# ProProject_stepper_music_2024-12-04.net
KiCad netlist of a schematic drawn in EasyEDA Pro
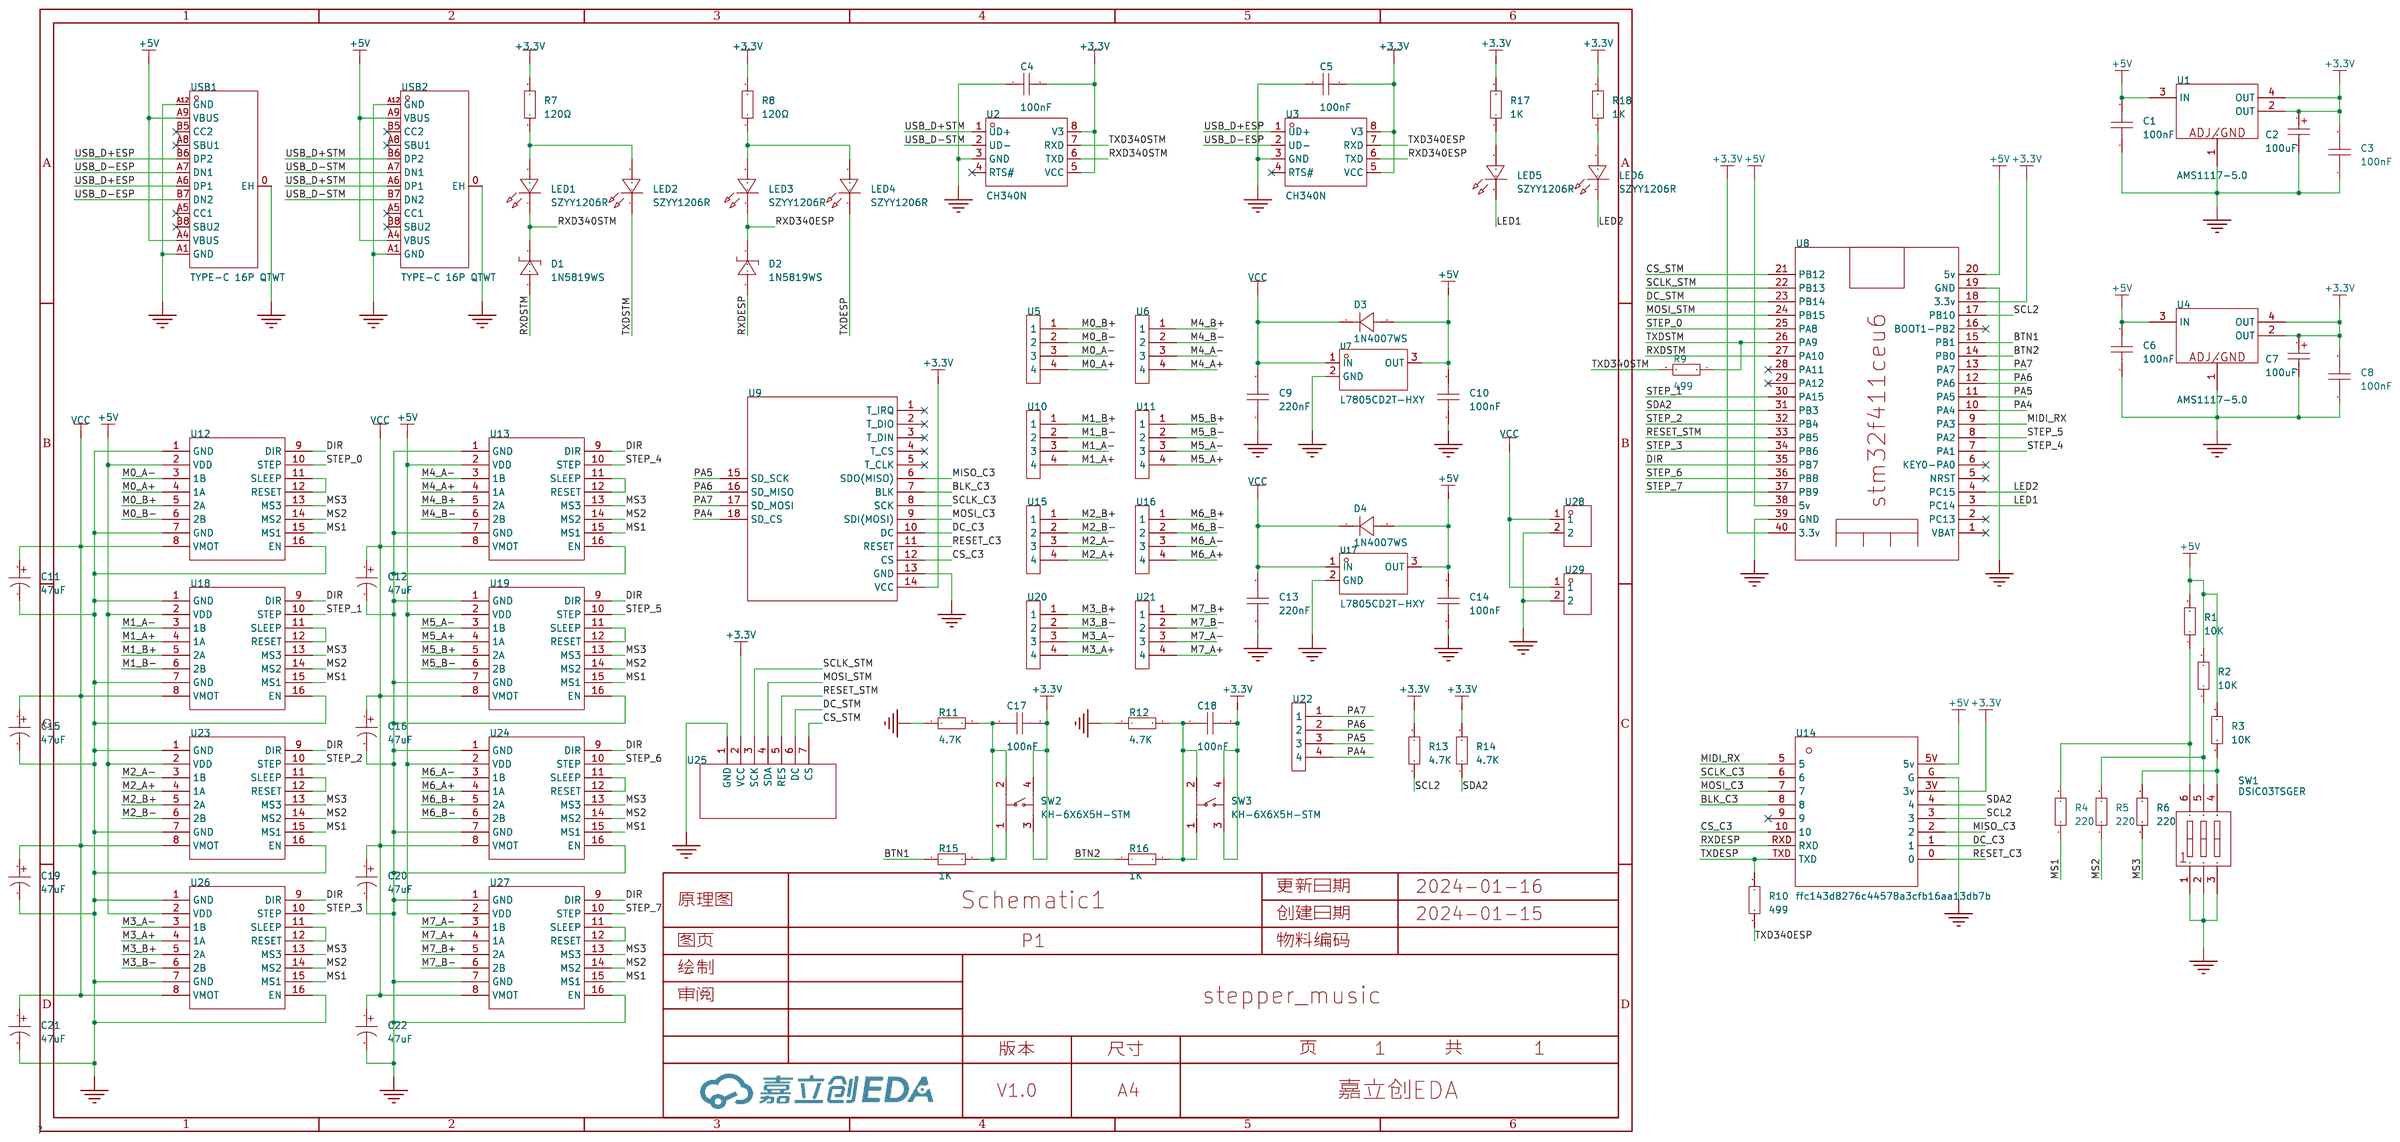
[diagram p0: schematic sheet]

(export (version "E")
  (design (tool "Eeschema 10.0.6"))
  (components
    (comp (ref "C1")
      (value "100nF")
      (footprint "easyedapro:C0603")
      (libsource (lib "easyedapro") (part "CapAcitance"))
    )
    (comp (ref "C2")
      (value "100uF")
      (footprint "easyedapro:CASE-D_7343")
      (description "容值:330uF;精度:±10%;额定电压:10V;等效串联电阻:900mΩ@100kHz;工作温度:-55°C~+125°C;")
      (fields (field (name "Manufacturer Part") "TAJD337K010RNJ") (field (name "Manufacturer") "Kyocera AVX"))
      (libsource (lib "easyedapro") (part "TAJD337K010RNJ"))
    )
    (comp (ref "C3")
      (value "100nF")
      (footprint "easyedapro:C0603")
      (libsource (lib "easyedapro") (part "CapAcitance"))
    )
    (comp (ref "C4")
      (value "100nF")
      (footprint "easyedapro:C0402")
      (description "容值:100nF;精度:±10%;额定电压:16V;材质(温度系数):X7R;")
      (fields
        (field (name "Manufacturer Part") "CL05B104KO5NNNC")
        (field (name "Manufacturer") "SAMSUNG(三星)")
      )
      (libsource (lib "easyedapro") (part "CL05B104KO5NNNC"))
    )
    (comp (ref "C5")
      (value "100nF")
      (footprint "easyedapro:C0402")
      (description "容值:100nF;精度:±10%;额定电压:16V;材质(温度系数):X7R;")
      (fields
        (field (name "Manufacturer Part") "CL05B104KO5NNNC")
        (field (name "Manufacturer") "SAMSUNG(三星)")
      )
      (libsource (lib "easyedapro") (part "CL05B104KO5NNNC"))
    )
    (comp (ref "C6")
      (value "100nF")
      (footprint "easyedapro:C0603")
      (libsource (lib "easyedapro") (part "CapAcitance"))
    )
    (comp (ref "C7")
      (value "100uF")
      (footprint "easyedapro:CASE-D_7343")
      (description "容值:330uF;精度:±10%;额定电压:10V;等效串联电阻:900mΩ@100kHz;工作温度:-55°C~+125°C;")
      (fields (field (name "Manufacturer Part") "TAJD337K010RNJ") (field (name "Manufacturer") "Kyocera AVX"))
      (libsource (lib "easyedapro") (part "TAJD337K010RNJ"))
    )
    (comp (ref "C8")
      (value "100nF")
      (footprint "easyedapro:C0603")
      (libsource (lib "easyedapro") (part "CapAcitance"))
    )
    (comp (ref "C9")
      (value "220nF")
      (footprint "easyedapro:C0603")
      (libsource (lib "easyedapro") (part "CapAcitance"))
    )
    (comp (ref "C10")
      (value "100nF")
      (footprint "easyedapro:C0603")
      (libsource (lib "easyedapro") (part "CapAcitance"))
    )
    (comp (ref "C11")
      (value "47uF")
      (footprint "easyedapro:CAP-TH_BD6.3-P2.50-D1.0-FD")
      (description "容值:47uF;精度:±20%;额定电压:50V;")
      (fields
        (field (name "Manufacturer Part") "KM476M050E11RR0VH2FP0")
        (field (name "Manufacturer") "CX(承兴)")
      )
      (libsource (lib "easyedapro") (part "47uF 50V 6.3*11_C45101"))
    )
    (comp (ref "C12")
      (value "47uF")
      (footprint "easyedapro:CAP-TH_BD6.3-P2.50-D1.0-FD")
      (description "容值:47uF;精度:±20%;额定电压:50V;")
      (fields
        (field (name "Manufacturer Part") "KM476M050E11RR0VH2FP0")
        (field (name "Manufacturer") "CX(承兴)")
      )
      (libsource (lib "easyedapro") (part "47uF 50V 6.3*11_C45101"))
    )
    (comp (ref "C13")
      (value "220nF")
      (footprint "easyedapro:C0603")
      (libsource (lib "easyedapro") (part "CapAcitance"))
    )
    (comp (ref "C14")
      (value "100nF")
      (footprint "easyedapro:C0603")
      (libsource (lib "easyedapro") (part "CapAcitance"))
    )
    (comp (ref "C15")
      (value "47uF")
      (footprint "easyedapro:CAP-TH_BD6.3-P2.50-D1.0-FD")
      (description "容值:47uF;精度:±20%;额定电压:50V;")
      (fields
        (field (name "Manufacturer Part") "KM476M050E11RR0VH2FP0")
        (field (name "Manufacturer") "CX(承兴)")
      )
      (libsource (lib "easyedapro") (part "47uF 50V 6.3*11_C45101"))
    )
    (comp (ref "C16")
      (value "47uF")
      (footprint "easyedapro:CAP-TH_BD6.3-P2.50-D1.0-FD")
      (description "容值:47uF;精度:±20%;额定电压:50V;")
      (fields
        (field (name "Manufacturer Part") "KM476M050E11RR0VH2FP0")
        (field (name "Manufacturer") "CX(承兴)")
      )
      (libsource (lib "easyedapro") (part "47uF 50V 6.3*11_C45101"))
    )
    (comp (ref "C17")
      (value "100nF")
      (footprint "easyedapro:C0603")
      (libsource (lib "easyedapro") (part "CapAcitance"))
    )
    (comp (ref "C18")
      (value "100nF")
      (footprint "easyedapro:C0603")
      (libsource (lib "easyedapro") (part "CapAcitance"))
    )
    (comp (ref "C19")
      (value "47uF")
      (footprint "easyedapro:CAP-TH_BD6.3-P2.50-D1.0-FD")
      (description "容值:47uF;精度:±20%;额定电压:50V;")
      (fields
        (field (name "Manufacturer Part") "KM476M050E11RR0VH2FP0")
        (field (name "Manufacturer") "CX(承兴)")
      )
      (libsource (lib "easyedapro") (part "47uF 50V 6.3*11_C45101"))
    )
    (comp (ref "C20")
      (value "47uF")
      (footprint "easyedapro:CAP-TH_BD6.3-P2.50-D1.0-FD")
      (description "容值:47uF;精度:±20%;额定电压:50V;")
      (fields
        (field (name "Manufacturer Part") "KM476M050E11RR0VH2FP0")
        (field (name "Manufacturer") "CX(承兴)")
      )
      (libsource (lib "easyedapro") (part "47uF 50V 6.3*11_C45101"))
    )
    (comp (ref "C21")
      (value "47uF")
      (footprint "easyedapro:CAP-TH_BD6.3-P2.50-D1.0-FD")
      (description "容值:47uF;精度:±20%;额定电压:50V;")
      (fields
        (field (name "Manufacturer Part") "KM476M050E11RR0VH2FP0")
        (field (name "Manufacturer") "CX(承兴)")
      )
      (libsource (lib "easyedapro") (part "47uF 50V 6.3*11_C45101"))
    )
    (comp (ref "C22")
      (value "47uF")
      (footprint "easyedapro:CAP-TH_BD6.3-P2.50-D1.0-FD")
      (description "容值:47uF;精度:±20%;额定电压:50V;")
      (fields
        (field (name "Manufacturer Part") "KM476M050E11RR0VH2FP0")
        (field (name "Manufacturer") "CX(承兴)")
      )
      (libsource (lib "easyedapro") (part "47uF 50V 6.3*11_C45101"))
    )
    (comp (ref "D1")
      (value "1N5819WS")
      (footprint "easyedapro:SOD-323_L1.8-W1.3-LS2.5-RD")
      (description "直流反向耐压(Vr):40V;平均整流电流(Io):1A;正向压降(Vf):600mV@1A;")
      (fields (field (name "Manufacturer") "Hottech(合科泰)"))
      (libsource (lib "easyedapro") (part "1N5819WS"))
    )
    (comp (ref "D2")
      (value "1N5819WS")
      (footprint "easyedapro:SOD-323_L1.8-W1.3-LS2.5-RD")
      (description "直流反向耐压(Vr):40V;平均整流电流(Io):1A;正向压降(Vf):600mV@1A;")
      (fields (field (name "Manufacturer") "Hottech(合科泰)"))
      (libsource (lib "easyedapro") (part "1N5819WS"))
    )
    (comp (ref "D3")
      (value "1N4007WS")
      (footprint "easyedapro:SOD-323_L1.6-W1.3-LS2.7-RD")
      (description "二极管配置:-;正向压降(Vf):1V@50mA;直流反向耐压(Vr):300V;平均整流电流(Io):300mA;")
      (fields (field (name "Manufacturer") "JSMSEMI(杰盛微)"))
      (libsource (lib "easyedapro") (part "1N4007WS_C2687395"))
    )
    (comp (ref "D4")
      (value "1N4007WS")
      (footprint "easyedapro:SOD-323_L1.6-W1.3-LS2.7-RD")
      (description "二极管配置:-;正向压降(Vf):1V@50mA;直流反向耐压(Vr):300V;平均整流电流(Io):300mA;")
      (fields (field (name "Manufacturer") "JSMSEMI(杰盛微)"))
      (libsource (lib "easyedapro") (part "1N4007WS_C2687395"))
    )
    (comp (ref "LED1")
      (value "SZYY1206R")
      (footprint "easyedapro:LED1206-RD-R_RED")
      (description "发光颜色:红灯;二极管配置:-;主波长:615nm~630nm;色温:-;功率:40mW;安装方式:-;")
      (fields (field (name "Manufacturer") "yongyu(永裕光电)"))
      (libsource (lib "easyedapro") (part "SZYY1206R"))
    )
    (comp (ref "LED2")
      (value "SZYY1206R")
      (footprint "easyedapro:LED1206-RD-R_RED")
      (description "发光颜色:红灯;二极管配置:-;主波长:615nm~630nm;色温:-;功率:40mW;安装方式:-;")
      (fields (field (name "Manufacturer") "yongyu(永裕光电)"))
      (libsource (lib "easyedapro") (part "SZYY1206R"))
    )
    (comp (ref "LED3")
      (value "SZYY1206R")
      (footprint "easyedapro:LED1206-RD-R_RED")
      (description "发光颜色:红灯;二极管配置:-;主波长:615nm~630nm;色温:-;功率:40mW;安装方式:-;")
      (fields (field (name "Manufacturer") "yongyu(永裕光电)"))
      (libsource (lib "easyedapro") (part "SZYY1206R"))
    )
    (comp (ref "LED4")
      (value "SZYY1206R")
      (footprint "easyedapro:LED1206-RD-R_RED")
      (description "发光颜色:红灯;二极管配置:-;主波长:615nm~630nm;色温:-;功率:40mW;安装方式:-;")
      (fields (field (name "Manufacturer") "yongyu(永裕光电)"))
      (libsource (lib "easyedapro") (part "SZYY1206R"))
    )
    (comp (ref "LED5")
      (value "SZYY1206R")
      (footprint "easyedapro:LED1206-RD-R_RED")
      (description "发光颜色:红灯;二极管配置:-;主波长:615nm~630nm;色温:-;功率:40mW;安装方式:-;")
      (fields (field (name "Manufacturer") "yongyu(永裕光电)"))
      (libsource (lib "easyedapro") (part "SZYY1206R"))
    )
    (comp (ref "LED6")
      (value "SZYY1206R")
      (footprint "easyedapro:LED1206-RD-R_RED")
      (description "发光颜色:红灯;二极管配置:-;主波长:615nm~630nm;色温:-;功率:40mW;安装方式:-;")
      (fields (field (name "Manufacturer") "yongyu(永裕光电)"))
      (libsource (lib "easyedapro") (part "SZYY1206R"))
    )
    (comp (ref "R1") (value "10K") (footprint "easyedapro:R0603") (libsource (lib "easyedapro") (part "电阻")))
    (comp (ref "R2") (value "10K") (footprint "easyedapro:R0603") (libsource (lib "easyedapro") (part "电阻")))
    (comp (ref "R3") (value "10K") (footprint "easyedapro:R0603") (libsource (lib "easyedapro") (part "电阻")))
    (comp (ref "R4") (value "220") (footprint "easyedapro:R0603") (libsource (lib "easyedapro") (part "电阻")))
    (comp (ref "R5") (value "220") (footprint "easyedapro:R0603") (libsource (lib "easyedapro") (part "电阻")))
    (comp (ref "R6") (value "220") (footprint "easyedapro:R0603") (libsource (lib "easyedapro") (part "电阻")))
    (comp (ref "R7")
      (value "120Ω")
      (footprint "easyedapro:R0603")
      (description "电阻类型:厚膜电阻;阻值:120Ω;精度:±1%;功率:100mW;")
      (fields
        (field (name "Manufacturer Part") "0603WAF1200T5E")
        (field (name "Manufacturer") "UNI-ROYAL(厚声)")
      )
      (libsource (lib "easyedapro") (part "0603WAF1200T5E"))
    )
    (comp (ref "R8")
      (value "120Ω")
      (footprint "easyedapro:R0603")
      (description "电阻类型:厚膜电阻;阻值:120Ω;精度:±1%;功率:100mW;")
      (fields
        (field (name "Manufacturer Part") "0603WAF1200T5E")
        (field (name "Manufacturer") "UNI-ROYAL(厚声)")
      )
      (libsource (lib "easyedapro") (part "0603WAF1200T5E"))
    )
    (comp (ref "R9") (value "499") (footprint "easyedapro:R0603") (libsource (lib "easyedapro") (part "电阻")))
    (comp (ref "R10") (value "499") (footprint "easyedapro:R0603") (libsource (lib "easyedapro") (part "电阻")))
    (comp (ref "R11")
      (value "4.7K")
      (footprint "easyedapro:R0603")
      (libsource (lib "easyedapro") (part "电阻"))
    )
    (comp (ref "R12")
      (value "4.7K")
      (footprint "easyedapro:R0603")
      (libsource (lib "easyedapro") (part "电阻"))
    )
    (comp (ref "R13")
      (value "4.7K")
      (footprint "easyedapro:R0603")
      (libsource (lib "easyedapro") (part "电阻"))
    )
    (comp (ref "R14")
      (value "4.7K")
      (footprint "easyedapro:R0603")
      (libsource (lib "easyedapro") (part "电阻"))
    )
    (comp (ref "R15") (value "1K") (footprint "easyedapro:R0603") (libsource (lib "easyedapro") (part "电阻")))
    (comp (ref "R16") (value "1K") (footprint "easyedapro:R0603") (libsource (lib "easyedapro") (part "电阻")))
    (comp (ref "R17") (value "1K") (footprint "easyedapro:R0603") (libsource (lib "easyedapro") (part "电阻")))
    (comp (ref "R18") (value "1K") (footprint "easyedapro:R0603") (libsource (lib "easyedapro") (part "电阻")))
    (comp (ref "SW1")
      (value "DSIC03TSGER")
      (footprint "easyedapro:SW-SMD_3P-L7.6-W6.0-P2.54-LS9.3-BL")
      (description "电路结构:单刀单掷;开关位数:3位;额定电流:25mA;额定电压:24V;使用寿命:3千次;颜色:黑色;")
      (fields (field (name "Manufacturer") "康深"))
      (libsource (lib "easyedapro") (part "DSIC03TSGER"))
    )
    (comp (ref "SW2")
      (value "KH-6X6X5H-STM")
      (footprint "easyedapro:SW-SMD_4P-L6.0-W6.0-P4.50-LS9.0-2")
      (description "电路结构:单刀单掷;带支架:否;触点电流:50mA;额定电压(DC):12V;安装方式:立贴;机械寿命:8万次;")
      (fields (field (name "Manufacturer") "kinghelm(金航标)"))
      (libsource (lib "easyedapro") (part "KH-6X6X5H-STM"))
    )
    (comp (ref "SW3")
      (value "KH-6X6X5H-STM")
      (footprint "easyedapro:SW-SMD_4P-L6.0-W6.0-P4.50-LS9.0-2")
      (description "电路结构:单刀单掷;带支架:否;触点电流:50mA;额定电压(DC):12V;安装方式:立贴;机械寿命:8万次;")
      (fields (field (name "Manufacturer") "kinghelm(金航标)"))
      (libsource (lib "easyedapro") (part "KH-6X6X5H-STM"))
    )
    (comp (ref "U1")
      (value "AMS1117-5.0")
      (footprint "easyedapro:SOT-223-3_L6.4-W3.5-P2.30-LS7.0-BR")
      (fields (field (name "Manufacturer") "国芯佳品"))
      (libsource (lib "easyedapro") (part "AMS1117-5.0_C2992571"))
    )
    (comp (ref "U2")
      (value "CH340N")
      (footprint "easyedapro:SOP-8_L4.9-W3.9-P1.27-LS6.0-BL")
      (fields (field (name "Manufacturer") "WCH(南京沁恒)"))
      (libsource (lib "easyedapro") (part "CH340N_C2977777"))
    )
    (comp (ref "U3")
      (value "CH340N")
      (footprint "easyedapro:SOP-8_L4.9-W3.9-P1.27-LS6.0-BL")
      (fields (field (name "Manufacturer") "WCH(南京沁恒)"))
      (libsource (lib "easyedapro") (part "CH340N_C2977777"))
    )
    (comp (ref "U4")
      (value "AMS1117-5.0")
      (footprint "easyedapro:SOT-223-3_L6.4-W3.5-P2.30-LS7.0-BR")
      (fields (field (name "Manufacturer") "国芯佳品"))
      (libsource (lib "easyedapro") (part "AMS1117-5.0_C2992571"))
    )
    (comp (ref "U5")
      (value "~")
      (footprint "easyedapro:2.54 - 4P")
      (description "间距2.54排针 4P")
      (libsource (lib "easyedapro") (part "2.54 - 4P"))
    )
    (comp (ref "U6")
      (value "~")
      (footprint "easyedapro:2.54 - 4P")
      (description "间距2.54排针 4P")
      (libsource (lib "easyedapro") (part "2.54 - 4P"))
    )
    (comp (ref "U7")
      (value "L7805CD2T-HXY")
      (footprint "easyedapro:TO-263-2_L10.2-W8.5-P2.54-LS15.2-TL")
      (description "输出类型:固定;最大输入电压:35V;输出电压:5V;输出电流:1A;输出极性:正;")
      (fields (field (name "Manufacturer") "HXY MOSFET(华轩阳电子)"))
      (libsource (lib "easyedapro") (part "L7805CD2T-HXY"))
    )
    (comp (ref "U8")
      (value "~")
      (footprint "easyedapro:stm32f411ceu6")
      (description "stm32f411ceu6\nhttps://www.taobao.com/list/item/594670660262.htm")
      (libsource (lib "easyedapro") (part "stm3f411ceu6"))
    )
    (comp (ref "U9")
      (value "~")
      (description "Driver: ILI9341")
      (libsource (lib "easyedapro") (part "2.8inch TFT LCD"))
    )
    (comp (ref "U10")
      (value "~")
      (footprint "easyedapro:2.54 - 4P")
      (description "间距2.54排针 4P")
      (libsource (lib "easyedapro") (part "2.54 - 4P"))
    )
    (comp (ref "U11")
      (value "~")
      (footprint "easyedapro:2.54 - 4P")
      (description "间距2.54排针 4P")
      (libsource (lib "easyedapro") (part "2.54 - 4P"))
    )
    (comp (ref "U12")
      (value "~")
      (footprint "easyedapro:a4988 module")
      (description "a4988 stepper motor driver module")
      (libsource (lib "easyedapro") (part "a4988"))
    )
    (comp (ref "U13")
      (value "~")
      (footprint "easyedapro:a4988 module")
      (description "a4988 stepper motor driver module")
      (libsource (lib "easyedapro") (part "a4988"))
    )
    (comp (ref "U14")
      (value "ffc143d8276c44578a3cfb16aa13db7b")
      (footprint "easyedapro:esp32c3-mini")
      (description "esp32c3-mini No-logo")
      (libsource (lib "easyedapro") (part "esp32c3_super_mini"))
    )
    (comp (ref "U15")
      (value "~")
      (footprint "easyedapro:2.54 - 4P")
      (description "间距2.54排针 4P")
      (libsource (lib "easyedapro") (part "2.54 - 4P"))
    )
    (comp (ref "U16")
      (value "~")
      (footprint "easyedapro:2.54 - 4P")
      (description "间距2.54排针 4P")
      (libsource (lib "easyedapro") (part "2.54 - 4P"))
    )
    (comp (ref "U17")
      (value "L7805CD2T-HXY")
      (footprint "easyedapro:TO-263-2_L10.2-W8.5-P2.54-LS15.2-TL")
      (description "输出类型:固定;最大输入电压:35V;输出电压:5V;输出电流:1A;输出极性:正;")
      (fields (field (name "Manufacturer") "HXY MOSFET(华轩阳电子)"))
      (libsource (lib "easyedapro") (part "L7805CD2T-HXY"))
    )
    (comp (ref "U18")
      (value "~")
      (footprint "easyedapro:a4988 module")
      (description "a4988 stepper motor driver module")
      (libsource (lib "easyedapro") (part "a4988"))
    )
    (comp (ref "U19")
      (value "~")
      (footprint "easyedapro:a4988 module")
      (description "a4988 stepper motor driver module")
      (libsource (lib "easyedapro") (part "a4988"))
    )
    (comp (ref "U20")
      (value "~")
      (footprint "easyedapro:2.54 - 4P")
      (description "间距2.54排针 4P")
      (libsource (lib "easyedapro") (part "2.54 - 4P"))
    )
    (comp (ref "U21")
      (value "~")
      (footprint "easyedapro:2.54 - 4P")
      (description "间距2.54排针 4P")
      (libsource (lib "easyedapro") (part "2.54 - 4P"))
    )
    (comp (ref "U22")
      (value "~")
      (footprint "easyedapro:2.54 - 4P")
      (description "间距2.54排针 4P")
      (libsource (lib "easyedapro") (part "2.54 - 4P"))
    )
    (comp (ref "U23")
      (value "~")
      (footprint "easyedapro:a4988 module")
      (description "a4988 stepper motor driver module")
      (libsource (lib "easyedapro") (part "a4988"))
    )
    (comp (ref "U24")
      (value "~")
      (footprint "easyedapro:a4988 module")
      (description "a4988 stepper motor driver module")
      (libsource (lib "easyedapro") (part "a4988"))
    )
    (comp (ref "U25")
      (value "~")
      (footprint "easyedapro:1.3inch OLED module")
      (description "SH1106 Driver 128*64")
      (libsource (lib "easyedapro") (part "1.3 inch OLED"))
    )
    (comp (ref "U26")
      (value "~")
      (footprint "easyedapro:a4988 module")
      (description "a4988 stepper motor driver module")
      (libsource (lib "easyedapro") (part "a4988"))
    )
    (comp (ref "U27")
      (value "~")
      (footprint "easyedapro:a4988 module")
      (description "a4988 stepper motor driver module")
      (libsource (lib "easyedapro") (part "a4988"))
    )
    (comp (ref "U28")
      (value "={Manufacturer Part} /")
      (footprint "easyedapro:CONN-TH_2P-P5.00_L7.6-W10.0")
      (fields
        (field (name "Manufacturer Part") "DB301V-5.0-2P-BU-S")
        (field (name "Manufacturer") "DIBO(地博电气)")
      )
      (libsource (lib "easyedapro") (part "DB301V-5.0-2P"))
    )
    (comp (ref "U29")
      (value "={Manufacturer Part} /")
      (footprint "easyedapro:CONN-TH_2P-P5.00_L7.6-W10.0")
      (fields
        (field (name "Manufacturer Part") "DB301V-5.0-2P-BU-S")
        (field (name "Manufacturer") "DIBO(地博电气)")
      )
      (libsource (lib "easyedapro") (part "DB301V-5.0-2P"))
    )
    (comp (ref "USB1")
      (value "TYPE-C 16P QTWT")
      (footprint "easyedapro:USB-TYPE-C-SMD_TYPE-C-16P-QTWT")
      (fields (field (name "Manufacturer") "SHOU HAN(首韩)"))
      (libsource (lib "easyedapro") (part "TYPE-C 16P QTWT"))
    )
    (comp (ref "USB2")
      (value "TYPE-C 16P QTWT")
      (footprint "easyedapro:USB-TYPE-C-SMD_TYPE-C-16P-QTWT")
      (fields (field (name "Manufacturer") "SHOU HAN(首韩)"))
      (libsource (lib "easyedapro") (part "TYPE-C 16P QTWT"))
    )
  )
  (nets
    (net (code "1") (name "+3.3V") (class "Default")
      (node (ref "C17") (pin "2") (pinfunction "2_2") (pintype "input"))
      (node (ref "C18") (pin "2") (pinfunction "2_2") (pintype "input"))
      (node (ref "C2") (pin "1") (pinfunction "1_1") (pintype "input"))
      (node (ref "C3") (pin "2") (pinfunction "2_2") (pintype "input"))
      (node (ref "C4") (pin "2") (pinfunction "2_2") (pintype "input"))
      (node (ref "C5") (pin "2") (pinfunction "2_2") (pintype "input"))
      (node (ref "C7") (pin "1") (pinfunction "1_1") (pintype "input"))
      (node (ref "C8") (pin "2") (pinfunction "2_2") (pintype "input"))
      (node (ref "R13") (pin "2") (pinfunction "2_2") (pintype "input"))
      (node (ref "R14") (pin "2") (pinfunction "2_2") (pintype "input"))
      (node (ref "R17") (pin "2") (pinfunction "2_2") (pintype "input"))
      (node (ref "R18") (pin "2") (pinfunction "2_2") (pintype "input"))
      (node (ref "R7") (pin "2") (pinfunction "2_2") (pintype "input"))
      (node (ref "R8") (pin "2") (pinfunction "2_2") (pintype "input"))
      (node (ref "SW2") (pin "3") (pinfunction "3_3") (pintype "unspecified"))
      (node (ref "SW2") (pin "4") (pinfunction "4_4") (pintype "unspecified"))
      (node (ref "SW3") (pin "3") (pinfunction "3_3") (pintype "unspecified"))
      (node (ref "SW3") (pin "4") (pinfunction "4_4") (pintype "unspecified"))
      (node (ref "U1") (pin "2") (pinfunction "OUT_2") (pintype "unspecified"))
      (node (ref "U1") (pin "4") (pinfunction "OUT_4") (pintype "unspecified"))
      (node (ref "U14") (pin "3V") (pinfunction "3v_3V") (pintype "input"))
      (node (ref "U2") (pin "5") (pinfunction "VCC_5") (pintype "input"))
      (node (ref "U2") (pin "8") (pinfunction "V3_8") (pintype "input"))
      (node (ref "U25") (pin "2") (pinfunction "VCC_2") (pintype "input"))
      (node (ref "U3") (pin "5") (pinfunction "VCC_5") (pintype "input"))
      (node (ref "U3") (pin "8") (pinfunction "V3_8") (pintype "input"))
      (node (ref "U4") (pin "2") (pinfunction "OUT_2") (pintype "unspecified"))
      (node (ref "U4") (pin "4") (pinfunction "OUT_4") (pintype "unspecified"))
      (node (ref "U8") (pin "18") (pinfunction "3.3v_18") (pintype "input"))
      (node (ref "U8") (pin "40") (pinfunction "3.3v_40") (pintype "input"))
      (node (ref "U9") (pin "14") (pinfunction "VCC_14") (pintype "input"))
    )
    (net (code "2") (name "+5V") (class "Default")
      (node (ref "C1") (pin "2") (pinfunction "2_2") (pintype "input"))
      (node (ref "C10") (pin "2") (pinfunction "2_2") (pintype "input"))
      (node (ref "C14") (pin "2") (pinfunction "2_2") (pintype "input"))
      (node (ref "C6") (pin "2") (pinfunction "2_2") (pintype "input"))
      (node (ref "D3") (pin "2") (pinfunction "A_2") (pintype "unspecified"))
      (node (ref "D4") (pin "2") (pinfunction "A_2") (pintype "unspecified"))
      (node (ref "R1") (pin "2") (pinfunction "2_2") (pintype "input"))
      (node (ref "R2") (pin "2") (pinfunction "2_2") (pintype "input"))
      (node (ref "R3") (pin "2") (pinfunction "2_2") (pintype "input"))
      (node (ref "U1") (pin "3") (pinfunction "IN_3") (pintype "unspecified"))
      (node (ref "U12") (pin "2") (pinfunction "VDD_2") (pintype "input"))
      (node (ref "U13") (pin "2") (pinfunction "VDD_2") (pintype "input"))
      (node (ref "U14") (pin "5V") (pinfunction "5v_5V") (pintype "input"))
      (node (ref "U17") (pin "3") (pinfunction "OUT_3") (pintype "input"))
      (node (ref "U18") (pin "2") (pinfunction "VDD_2") (pintype "input"))
      (node (ref "U19") (pin "2") (pinfunction "VDD_2") (pintype "input"))
      (node (ref "U23") (pin "2") (pinfunction "VDD_2") (pintype "input"))
      (node (ref "U24") (pin "2") (pinfunction "VDD_2") (pintype "input"))
      (node (ref "U26") (pin "2") (pinfunction "VDD_2") (pintype "input"))
      (node (ref "U27") (pin "2") (pinfunction "VDD_2") (pintype "input"))
      (node (ref "U4") (pin "3") (pinfunction "IN_3") (pintype "unspecified"))
      (node (ref "U7") (pin "3") (pinfunction "OUT_3") (pintype "input"))
      (node (ref "U8") (pin "20") (pinfunction "5v_20") (pintype "input"))
      (node (ref "U8") (pin "38") (pinfunction "5v_38") (pintype "input"))
      (node (ref "USB1") (pin "A4") (pinfunction "VBUS_A4") (pintype "unspecified"))
      (node (ref "USB1") (pin "A9") (pinfunction "VBUS_A9") (pintype "unspecified"))
      (node (ref "USB2") (pin "A4") (pinfunction "VBUS_A4") (pintype "unspecified"))
      (node (ref "USB2") (pin "A9") (pinfunction "VBUS_A9") (pintype "unspecified"))
    )
    (net (code "3") (name "/BLK_C3") (class "Default")
      (node (ref "U14") (pin "8") (pinfunction "8_8") (pintype "input"))
      (node (ref "U9") (pin "7") (pinfunction "BLK_7") (pintype "input"))
    )
    (net (code "4") (name "/BTN1") (class "Default")
      (node (ref "R15") (pin "1") (pinfunction "1_1") (pintype "input"))
      (node (ref "U8") (pin "15") (pinfunction "PB1_15") (pintype "input"))
    )
    (net (code "5") (name "/BTN2") (class "Default")
      (node (ref "R16") (pin "1") (pinfunction "1_1") (pintype "input"))
      (node (ref "U8") (pin "14") (pinfunction "PB0_14") (pintype "input"))
    )
    (net (code "6") (name "/CS_C3") (class "Default")
      (node (ref "U14") (pin "10") (pinfunction "10_10") (pintype "input"))
      (node (ref "U9") (pin "12") (pinfunction "CS_12") (pintype "input"))
    )
    (net (code "7") (name "/CS_STM") (class "Default")
      (node (ref "U25") (pin "7") (pinfunction "CS_7") (pintype "input"))
      (node (ref "U8") (pin "21") (pinfunction "PB12_21") (pintype "input"))
    )
    (net (code "8") (name "/DC_C3") (class "Default")
      (node (ref "U14") (pin "1") (pinfunction "1_1") (pintype "bidirectional"))
      (node (ref "U9") (pin "10") (pinfunction "DC_10") (pintype "input"))
    )
    (net (code "9") (name "/DC_STM") (class "Default")
      (node (ref "U25") (pin "6") (pinfunction "DC_6") (pintype "input"))
      (node (ref "U8") (pin "23") (pinfunction "PB14_23") (pintype "input"))
    )
    (net (code "10") (name "/DIR") (class "Default")
      (node (ref "U12") (pin "9") (pinfunction "DIR_9") (pintype "input"))
      (node (ref "U13") (pin "9") (pinfunction "DIR_9") (pintype "input"))
      (node (ref "U18") (pin "9") (pinfunction "DIR_9") (pintype "input"))
      (node (ref "U19") (pin "9") (pinfunction "DIR_9") (pintype "input"))
      (node (ref "U23") (pin "9") (pinfunction "DIR_9") (pintype "input"))
      (node (ref "U24") (pin "9") (pinfunction "DIR_9") (pintype "input"))
      (node (ref "U26") (pin "9") (pinfunction "DIR_9") (pintype "input"))
      (node (ref "U27") (pin "9") (pinfunction "DIR_9") (pintype "input"))
      (node (ref "U8") (pin "35") (pinfunction "PB7_35") (pintype "input"))
    )
    (net (code "11") (name "/LED1") (class "Default")
      (node (ref "LED5") (pin "1") (pinfunction "1_1") (pintype "input"))
      (node (ref "U8") (pin "3") (pinfunction "PC14_3") (pintype "input"))
    )
    (net (code "12") (name "/LED2") (class "Default")
      (node (ref "LED6") (pin "1") (pinfunction "1_1") (pintype "input"))
      (node (ref "U8") (pin "4") (pinfunction "PC15_4") (pintype "input"))
    )
    (net (code "13") (name "/M0_A+") (class "Default")
      (node (ref "U12") (pin "4") (pinfunction "1A_4") (pintype "input"))
      (node (ref "U5") (pin "4") (pinfunction "4_4") (pintype "input"))
    )
    (net (code "14") (name "/M0_A-") (class "Default")
      (node (ref "U12") (pin "3") (pinfunction "1B_3") (pintype "input"))
      (node (ref "U5") (pin "3") (pinfunction "3_3") (pintype "input"))
    )
    (net (code "15") (name "/M0_B+") (class "Default")
      (node (ref "U12") (pin "5") (pinfunction "2A_5") (pintype "input"))
      (node (ref "U5") (pin "1") (pinfunction "1_1") (pintype "input"))
    )
    (net (code "16") (name "/M0_B-") (class "Default")
      (node (ref "U12") (pin "6") (pinfunction "2B_6") (pintype "input"))
      (node (ref "U5") (pin "2") (pinfunction "2_2") (pintype "input"))
    )
    (net (code "17") (name "/M1_A+") (class "Default")
      (node (ref "U10") (pin "4") (pinfunction "4_4") (pintype "input"))
      (node (ref "U18") (pin "4") (pinfunction "1A_4") (pintype "input"))
    )
    (net (code "18") (name "/M1_A-") (class "Default")
      (node (ref "U10") (pin "3") (pinfunction "3_3") (pintype "input"))
      (node (ref "U18") (pin "3") (pinfunction "1B_3") (pintype "input"))
    )
    (net (code "19") (name "/M1_B+") (class "Default")
      (node (ref "U10") (pin "1") (pinfunction "1_1") (pintype "input"))
      (node (ref "U18") (pin "5") (pinfunction "2A_5") (pintype "input"))
    )
    (net (code "20") (name "/M1_B-") (class "Default")
      (node (ref "U10") (pin "2") (pinfunction "2_2") (pintype "input"))
      (node (ref "U18") (pin "6") (pinfunction "2B_6") (pintype "input"))
    )
    (net (code "21") (name "/M2_A+") (class "Default")
      (node (ref "U15") (pin "4") (pinfunction "4_4") (pintype "input"))
      (node (ref "U23") (pin "4") (pinfunction "1A_4") (pintype "input"))
    )
    (net (code "22") (name "/M2_A-") (class "Default")
      (node (ref "U15") (pin "3") (pinfunction "3_3") (pintype "input"))
      (node (ref "U23") (pin "3") (pinfunction "1B_3") (pintype "input"))
    )
    (net (code "23") (name "/M2_B+") (class "Default")
      (node (ref "U15") (pin "1") (pinfunction "1_1") (pintype "input"))
      (node (ref "U23") (pin "5") (pinfunction "2A_5") (pintype "input"))
    )
    (net (code "24") (name "/M2_B-") (class "Default")
      (node (ref "U15") (pin "2") (pinfunction "2_2") (pintype "input"))
      (node (ref "U23") (pin "6") (pinfunction "2B_6") (pintype "input"))
    )
    (net (code "25") (name "/M3_A+") (class "Default")
      (node (ref "U20") (pin "4") (pinfunction "4_4") (pintype "input"))
      (node (ref "U26") (pin "4") (pinfunction "1A_4") (pintype "input"))
    )
    (net (code "26") (name "/M3_A-") (class "Default")
      (node (ref "U20") (pin "3") (pinfunction "3_3") (pintype "input"))
      (node (ref "U26") (pin "3") (pinfunction "1B_3") (pintype "input"))
    )
    (net (code "27") (name "/M3_B+") (class "Default")
      (node (ref "U20") (pin "1") (pinfunction "1_1") (pintype "input"))
      (node (ref "U26") (pin "5") (pinfunction "2A_5") (pintype "input"))
    )
    (net (code "28") (name "/M3_B-") (class "Default")
      (node (ref "U20") (pin "2") (pinfunction "2_2") (pintype "input"))
      (node (ref "U26") (pin "6") (pinfunction "2B_6") (pintype "input"))
    )
    (net (code "29") (name "/M4_A+") (class "Default")
      (node (ref "U13") (pin "4") (pinfunction "1A_4") (pintype "input"))
      (node (ref "U6") (pin "4") (pinfunction "4_4") (pintype "input"))
    )
    (net (code "30") (name "/M4_A-") (class "Default")
      (node (ref "U13") (pin "3") (pinfunction "1B_3") (pintype "input"))
      (node (ref "U6") (pin "3") (pinfunction "3_3") (pintype "input"))
    )
    (net (code "31") (name "/M4_B+") (class "Default")
      (node (ref "U13") (pin "5") (pinfunction "2A_5") (pintype "input"))
      (node (ref "U6") (pin "1") (pinfunction "1_1") (pintype "input"))
    )
    (net (code "32") (name "/M4_B-") (class "Default")
      (node (ref "U13") (pin "6") (pinfunction "2B_6") (pintype "input"))
      (node (ref "U6") (pin "2") (pinfunction "2_2") (pintype "input"))
    )
    (net (code "33") (name "/M5_A+") (class "Default")
      (node (ref "U11") (pin "4") (pinfunction "4_4") (pintype "input"))
      (node (ref "U19") (pin "4") (pinfunction "1A_4") (pintype "input"))
    )
    (net (code "34") (name "/M5_A-") (class "Default")
      (node (ref "U11") (pin "3") (pinfunction "3_3") (pintype "input"))
      (node (ref "U19") (pin "3") (pinfunction "1B_3") (pintype "input"))
    )
    (net (code "35") (name "/M5_B+") (class "Default")
      (node (ref "U11") (pin "1") (pinfunction "1_1") (pintype "input"))
      (node (ref "U19") (pin "5") (pinfunction "2A_5") (pintype "input"))
    )
    (net (code "36") (name "/M5_B-") (class "Default")
      (node (ref "U11") (pin "2") (pinfunction "2_2") (pintype "input"))
      (node (ref "U19") (pin "6") (pinfunction "2B_6") (pintype "input"))
    )
    (net (code "37") (name "/M6_A+") (class "Default")
      (node (ref "U16") (pin "4") (pinfunction "4_4") (pintype "input"))
      (node (ref "U24") (pin "4") (pinfunction "1A_4") (pintype "input"))
    )
    (net (code "38") (name "/M6_A-") (class "Default")
      (node (ref "U16") (pin "3") (pinfunction "3_3") (pintype "input"))
      (node (ref "U24") (pin "3") (pinfunction "1B_3") (pintype "input"))
    )
    (net (code "39") (name "/M6_B+") (class "Default")
      (node (ref "U16") (pin "1") (pinfunction "1_1") (pintype "input"))
      (node (ref "U24") (pin "5") (pinfunction "2A_5") (pintype "input"))
    )
    (net (code "40") (name "/M6_B-") (class "Default")
      (node (ref "U16") (pin "2") (pinfunction "2_2") (pintype "input"))
      (node (ref "U24") (pin "6") (pinfunction "2B_6") (pintype "input"))
    )
    (net (code "41") (name "/M7_A+") (class "Default")
      (node (ref "U21") (pin "4") (pinfunction "4_4") (pintype "input"))
      (node (ref "U27") (pin "4") (pinfunction "1A_4") (pintype "input"))
    )
    (net (code "42") (name "/M7_A-") (class "Default")
      (node (ref "U21") (pin "3") (pinfunction "3_3") (pintype "input"))
      (node (ref "U27") (pin "3") (pinfunction "1B_3") (pintype "input"))
    )
    (net (code "43") (name "/M7_B+") (class "Default")
      (node (ref "U21") (pin "1") (pinfunction "1_1") (pintype "input"))
      (node (ref "U27") (pin "5") (pinfunction "2A_5") (pintype "input"))
    )
    (net (code "44") (name "/M7_B-") (class "Default")
      (node (ref "U21") (pin "2") (pinfunction "2_2") (pintype "input"))
      (node (ref "U27") (pin "6") (pinfunction "2B_6") (pintype "input"))
    )
    (net (code "45") (name "/MIDI_RX") (class "Default")
      (node (ref "U14") (pin "5") (pinfunction "5_5") (pintype "input"))
      (node (ref "U8") (pin "9") (pinfunction "PA3_9") (pintype "input"))
    )
    (net (code "46") (name "/MISO_C3") (class "Default")
      (node (ref "U14") (pin "2") (pinfunction "2_2") (pintype "bidirectional"))
      (node (ref "U9") (pin "6") (pinfunction "SDO(MISO)_6") (pintype "input"))
    )
    (net (code "47") (name "/MOSI_C3") (class "Default")
      (node (ref "U14") (pin "7") (pinfunction "7_7") (pintype "input"))
      (node (ref "U9") (pin "9") (pinfunction "SDI(MOSI)_9") (pintype "input"))
    )
    (net (code "48") (name "/MOSI_STM") (class "Default")
      (node (ref "U25") (pin "4") (pinfunction "SDA_4") (pintype "input"))
      (node (ref "U8") (pin "24") (pinfunction "PB15_24") (pintype "input"))
    )
    (net (code "49") (name "/MS1") (class "Default")
      (node (ref "R4") (pin "1") (pinfunction "1_1") (pintype "input"))
      (node (ref "U12") (pin "15") (pinfunction "MS1_15") (pintype "input"))
      (node (ref "U13") (pin "15") (pinfunction "MS1_15") (pintype "input"))
      (node (ref "U18") (pin "15") (pinfunction "MS1_15") (pintype "input"))
      (node (ref "U19") (pin "15") (pinfunction "MS1_15") (pintype "input"))
      (node (ref "U23") (pin "15") (pinfunction "MS1_15") (pintype "input"))
      (node (ref "U24") (pin "15") (pinfunction "MS1_15") (pintype "input"))
      (node (ref "U26") (pin "15") (pinfunction "MS1_15") (pintype "input"))
      (node (ref "U27") (pin "15") (pinfunction "MS1_15") (pintype "input"))
    )
    (net (code "50") (name "/MS2") (class "Default")
      (node (ref "R5") (pin "1") (pinfunction "1_1") (pintype "input"))
      (node (ref "U12") (pin "14") (pinfunction "MS2_14") (pintype "input"))
      (node (ref "U13") (pin "14") (pinfunction "MS2_14") (pintype "input"))
      (node (ref "U18") (pin "14") (pinfunction "MS2_14") (pintype "input"))
      (node (ref "U19") (pin "14") (pinfunction "MS2_14") (pintype "input"))
      (node (ref "U23") (pin "14") (pinfunction "MS2_14") (pintype "input"))
      (node (ref "U24") (pin "14") (pinfunction "MS2_14") (pintype "input"))
      (node (ref "U26") (pin "14") (pinfunction "MS2_14") (pintype "input"))
      (node (ref "U27") (pin "14") (pinfunction "MS2_14") (pintype "input"))
    )
    (net (code "51") (name "/MS3") (class "Default")
      (node (ref "R6") (pin "1") (pinfunction "1_1") (pintype "input"))
      (node (ref "U12") (pin "13") (pinfunction "MS3_13") (pintype "input"))
      (node (ref "U13") (pin "13") (pinfunction "MS3_13") (pintype "input"))
      (node (ref "U18") (pin "13") (pinfunction "MS3_13") (pintype "input"))
      (node (ref "U19") (pin "13") (pinfunction "MS3_13") (pintype "input"))
      (node (ref "U23") (pin "13") (pinfunction "MS3_13") (pintype "input"))
      (node (ref "U24") (pin "13") (pinfunction "MS3_13") (pintype "input"))
      (node (ref "U26") (pin "13") (pinfunction "MS3_13") (pintype "input"))
      (node (ref "U27") (pin "13") (pinfunction "MS3_13") (pintype "input"))
    )
    (net (code "52") (name "/PA4") (class "Default")
      (node (ref "U22") (pin "4") (pinfunction "4_4") (pintype "input"))
      (node (ref "U8") (pin "10") (pinfunction "PA4_10") (pintype "input"))
      (node (ref "U9") (pin "18") (pinfunction "SD_CS_18") (pintype "input"))
    )
    (net (code "53") (name "/PA5") (class "Default")
      (node (ref "U22") (pin "3") (pinfunction "3_3") (pintype "input"))
      (node (ref "U8") (pin "11") (pinfunction "PA5_11") (pintype "input"))
      (node (ref "U9") (pin "15") (pinfunction "SD_SCK_15") (pintype "input"))
    )
    (net (code "54") (name "/PA6") (class "Default")
      (node (ref "U22") (pin "2") (pinfunction "2_2") (pintype "input"))
      (node (ref "U8") (pin "12") (pinfunction "PA6_12") (pintype "input"))
      (node (ref "U9") (pin "16") (pinfunction "SD_MISO_16") (pintype "input"))
    )
    (net (code "55") (name "/PA7") (class "Default")
      (node (ref "U22") (pin "1") (pinfunction "1_1") (pintype "input"))
      (node (ref "U8") (pin "13") (pinfunction "PA7_13") (pintype "input"))
      (node (ref "U9") (pin "17") (pinfunction "SD_MOSI_17") (pintype "input"))
    )
    (net (code "56") (name "/RESET_C3") (class "Default")
      (node (ref "U14") (pin "0") (pinfunction "0_0") (pintype "bidirectional"))
      (node (ref "U9") (pin "11") (pinfunction "RESET_11") (pintype "input"))
    )
    (net (code "57") (name "/RESET_STM") (class "Default")
      (node (ref "U25") (pin "5") (pinfunction "RES_5") (pintype "input"))
      (node (ref "U8") (pin "33") (pinfunction "PB5_33") (pintype "input"))
    )
    (net (code "58") (name "/RXD340ESP") (class "Default")
      (node (ref "D2") (pin "1") (pinfunction "C_1") (pintype "input"))
      (node (ref "LED3") (pin "1") (pinfunction "1_1") (pintype "input"))
      (node (ref "U3") (pin "6") (pinfunction "TXD_6") (pintype "input"))
    )
    (net (code "59") (name "/RXD340STM") (class "Default")
      (node (ref "D1") (pin "1") (pinfunction "C_1") (pintype "input"))
      (node (ref "LED1") (pin "1") (pinfunction "1_1") (pintype "input"))
      (node (ref "U2") (pin "6") (pinfunction "TXD_6") (pintype "input"))
    )
    (net (code "60") (name "/RXDESP") (class "Default")
      (node (ref "D2") (pin "2") (pinfunction "A_2") (pintype "input"))
      (node (ref "U14") (pin "RXD") (pinfunction "RXD_RXD") (pintype "input"))
    )
    (net (code "61") (name "/RXDSTM") (class "Default")
      (node (ref "D1") (pin "2") (pinfunction "A_2") (pintype "input"))
      (node (ref "U8") (pin "27") (pinfunction "PA10_27") (pintype "input"))
    )
    (net (code "62") (name "/SCL2") (class "Default")
      (node (ref "R13") (pin "1") (pinfunction "1_1") (pintype "input"))
      (node (ref "U14") (pin "3") (pinfunction "3_3") (pintype "bidirectional"))
      (node (ref "U8") (pin "17") (pinfunction "PB10_17") (pintype "input"))
    )
    (net (code "63") (name "/SCLK_C3") (class "Default")
      (node (ref "U14") (pin "6") (pinfunction "6_6") (pintype "input"))
      (node (ref "U9") (pin "8") (pinfunction "SCK_8") (pintype "input"))
    )
    (net (code "64") (name "/SCLK_STM") (class "Default")
      (node (ref "U25") (pin "3") (pinfunction "SCK_3") (pintype "input"))
      (node (ref "U8") (pin "22") (pinfunction "PB13_22") (pintype "input"))
    )
    (net (code "65") (name "/SDA2") (class "Default")
      (node (ref "R14") (pin "1") (pinfunction "1_1") (pintype "input"))
      (node (ref "U14") (pin "4") (pinfunction "4_4") (pintype "bidirectional"))
      (node (ref "U8") (pin "31") (pinfunction "PB3_31") (pintype "input"))
    )
    (net (code "66") (name "/STEP_0") (class "Default")
      (node (ref "U12") (pin "10") (pinfunction "STEP_10") (pintype "input"))
      (node (ref "U8") (pin "25") (pinfunction "PA8_25") (pintype "input"))
    )
    (net (code "67") (name "/STEP_1") (class "Default")
      (node (ref "U18") (pin "10") (pinfunction "STEP_10") (pintype "input"))
      (node (ref "U8") (pin "30") (pinfunction "PA15_30") (pintype "input"))
    )
    (net (code "68") (name "/STEP_2") (class "Default")
      (node (ref "U23") (pin "10") (pinfunction "STEP_10") (pintype "input"))
      (node (ref "U8") (pin "32") (pinfunction "PB4_32") (pintype "input"))
    )
    (net (code "69") (name "/STEP_3") (class "Default")
      (node (ref "U26") (pin "10") (pinfunction "STEP_10") (pintype "input"))
      (node (ref "U8") (pin "34") (pinfunction "PB6_34") (pintype "input"))
    )
    (net (code "70") (name "/STEP_4") (class "Default")
      (node (ref "U13") (pin "10") (pinfunction "STEP_10") (pintype "input"))
      (node (ref "U8") (pin "7") (pinfunction "PA1_7") (pintype "input"))
    )
    (net (code "71") (name "/STEP_5") (class "Default")
      (node (ref "U19") (pin "10") (pinfunction "STEP_10") (pintype "input"))
      (node (ref "U8") (pin "8") (pinfunction "PA2_8") (pintype "input"))
    )
    (net (code "72") (name "/STEP_6") (class "Default")
      (node (ref "U24") (pin "10") (pinfunction "STEP_10") (pintype "input"))
      (node (ref "U8") (pin "36") (pinfunction "PB8_36") (pintype "input"))
    )
    (net (code "73") (name "/STEP_7") (class "Default")
      (node (ref "U27") (pin "10") (pinfunction "STEP_10") (pintype "input"))
      (node (ref "U8") (pin "37") (pinfunction "PB9_37") (pintype "input"))
    )
    (net (code "74") (name "/TXD340ESP") (class "Default")
      (node (ref "R10") (pin "1") (pinfunction "1_1") (pintype "input"))
      (node (ref "U3") (pin "7") (pinfunction "RXD_7") (pintype "input"))
    )
    (net (code "75") (name "/TXD340STM") (class "Default")
      (node (ref "R9") (pin "2") (pinfunction "2_2") (pintype "input"))
      (node (ref "U2") (pin "7") (pinfunction "RXD_7") (pintype "input"))
    )
    (net (code "76") (name "/TXDESP") (class "Default")
      (node (ref "LED4") (pin "1") (pinfunction "1_1") (pintype "input"))
      (node (ref "R10") (pin "2") (pinfunction "2_2") (pintype "input"))
      (node (ref "U14") (pin "TXD") (pinfunction "TXD_TXD") (pintype "bidirectional"))
    )
    (net (code "77") (name "/TXDSTM") (class "Default")
      (node (ref "LED2") (pin "1") (pinfunction "1_1") (pintype "input"))
      (node (ref "R9") (pin "1") (pinfunction "1_1") (pintype "input"))
      (node (ref "U8") (pin "26") (pinfunction "PA9_26") (pintype "input"))
    )
    (net (code "78") (name "/USB_D+ESP") (class "Default")
      (node (ref "U3") (pin "1") (pinfunction "UD+_1") (pintype "input"))
      (node (ref "USB1") (pin "A6") (pinfunction "DP1_A6") (pintype "unspecified"))
      (node (ref "USB1") (pin "B6") (pinfunction "DP2_B6") (pintype "unspecified"))
    )
    (net (code "79") (name "/USB_D+STM") (class "Default")
      (node (ref "U2") (pin "1") (pinfunction "UD+_1") (pintype "input"))
      (node (ref "USB2") (pin "A6") (pinfunction "DP1_A6") (pintype "unspecified"))
      (node (ref "USB2") (pin "B6") (pinfunction "DP2_B6") (pintype "unspecified"))
    )
    (net (code "80") (name "/USB_D-ESP") (class "Default")
      (node (ref "U3") (pin "2") (pinfunction "UD-_2") (pintype "input"))
      (node (ref "USB1") (pin "A7") (pinfunction "DN1_A7") (pintype "unspecified"))
      (node (ref "USB1") (pin "B7") (pinfunction "DN2_B7") (pintype "unspecified"))
    )
    (net (code "81") (name "/USB_D-STM") (class "Default")
      (node (ref "U2") (pin "2") (pinfunction "UD-_2") (pintype "input"))
      (node (ref "USB2") (pin "A7") (pinfunction "DN1_A7") (pintype "unspecified"))
      (node (ref "USB2") (pin "B7") (pinfunction "DN2_B7") (pintype "unspecified"))
    )
    (net (code "82") (name "GND") (class "Default")
      (node (ref "C1") (pin "1") (pinfunction "1_1") (pintype "input"))
      (node (ref "C10") (pin "1") (pinfunction "1_1") (pintype "input"))
      (node (ref "C11") (pin "2") (pinfunction "2_2") (pintype "input"))
      (node (ref "C12") (pin "2") (pinfunction "2_2") (pintype "input"))
      (node (ref "C13") (pin "1") (pinfunction "1_1") (pintype "input"))
      (node (ref "C14") (pin "1") (pinfunction "1_1") (pintype "input"))
      (node (ref "C15") (pin "2") (pinfunction "2_2") (pintype "input"))
      (node (ref "C16") (pin "2") (pinfunction "2_2") (pintype "input"))
      (node (ref "C19") (pin "2") (pinfunction "2_2") (pintype "input"))
      (node (ref "C2") (pin "2") (pinfunction "2_2") (pintype "input"))
      (node (ref "C20") (pin "2") (pinfunction "2_2") (pintype "input"))
      (node (ref "C21") (pin "2") (pinfunction "2_2") (pintype "input"))
      (node (ref "C22") (pin "2") (pinfunction "2_2") (pintype "input"))
      (node (ref "C3") (pin "1") (pinfunction "1_1") (pintype "input"))
      (node (ref "C4") (pin "1") (pinfunction "1_1") (pintype "input"))
      (node (ref "C5") (pin "1") (pinfunction "1_1") (pintype "input"))
      (node (ref "C6") (pin "1") (pinfunction "1_1") (pintype "input"))
      (node (ref "C7") (pin "2") (pinfunction "2_2") (pintype "input"))
      (node (ref "C8") (pin "1") (pinfunction "1_1") (pintype "input"))
      (node (ref "C9") (pin "1") (pinfunction "1_1") (pintype "input"))
      (node (ref "R11") (pin "1") (pinfunction "1_1") (pintype "input"))
      (node (ref "R12") (pin "1") (pinfunction "1_1") (pintype "input"))
      (node (ref "SW1") (pin "1") (pinfunction "A1_1") (pintype "input"))
      (node (ref "SW1") (pin "2") (pinfunction "A2_2") (pintype "input"))
      (node (ref "SW1") (pin "3") (pinfunction "A3_3") (pintype "input"))
      (node (ref "U1") (pin "1") (pinfunction "ADJ/GND_1") (pintype "unspecified"))
      (node (ref "U12") (pin "1") (pinfunction "GND_1") (pintype "input"))
      (node (ref "U12") (pin "16") (pinfunction "EN_16") (pintype "input"))
      (node (ref "U12") (pin "7") (pinfunction "GND_7") (pintype "input"))
      (node (ref "U13") (pin "1") (pinfunction "GND_1") (pintype "input"))
      (node (ref "U13") (pin "16") (pinfunction "EN_16") (pintype "input"))
      (node (ref "U13") (pin "7") (pinfunction "GND_7") (pintype "input"))
      (node (ref "U14") (pin "G") (pinfunction "G_G") (pintype "input"))
      (node (ref "U17") (pin "2") (pinfunction "GND_2") (pintype "input"))
      (node (ref "U18") (pin "1") (pinfunction "GND_1") (pintype "input"))
      (node (ref "U18") (pin "16") (pinfunction "EN_16") (pintype "input"))
      (node (ref "U18") (pin "7") (pinfunction "GND_7") (pintype "input"))
      (node (ref "U19") (pin "1") (pinfunction "GND_1") (pintype "input"))
      (node (ref "U19") (pin "16") (pinfunction "EN_16") (pintype "input"))
      (node (ref "U19") (pin "7") (pinfunction "GND_7") (pintype "input"))
      (node (ref "U2") (pin "3") (pinfunction "GND_3") (pintype "input"))
      (node (ref "U23") (pin "1") (pinfunction "GND_1") (pintype "input"))
      (node (ref "U23") (pin "16") (pinfunction "EN_16") (pintype "input"))
      (node (ref "U23") (pin "7") (pinfunction "GND_7") (pintype "input"))
      (node (ref "U24") (pin "1") (pinfunction "GND_1") (pintype "input"))
      (node (ref "U24") (pin "16") (pinfunction "EN_16") (pintype "input"))
      (node (ref "U24") (pin "7") (pinfunction "GND_7") (pintype "input"))
      (node (ref "U25") (pin "1") (pinfunction "GND_1") (pintype "input"))
      (node (ref "U26") (pin "1") (pinfunction "GND_1") (pintype "input"))
      (node (ref "U26") (pin "16") (pinfunction "EN_16") (pintype "input"))
      (node (ref "U26") (pin "7") (pinfunction "GND_7") (pintype "input"))
      (node (ref "U27") (pin "1") (pinfunction "GND_1") (pintype "input"))
      (node (ref "U27") (pin "16") (pinfunction "EN_16") (pintype "input"))
      (node (ref "U27") (pin "7") (pinfunction "GND_7") (pintype "input"))
      (node (ref "U28") (pin "2") (pinfunction "2_2") (pintype "unspecified"))
      (node (ref "U29") (pin "2") (pinfunction "2_2") (pintype "unspecified"))
      (node (ref "U3") (pin "3") (pinfunction "GND_3") (pintype "input"))
      (node (ref "U4") (pin "1") (pinfunction "ADJ/GND_1") (pintype "unspecified"))
      (node (ref "U7") (pin "2") (pinfunction "GND_2") (pintype "input"))
      (node (ref "U8") (pin "19") (pinfunction "GND_19") (pintype "input"))
      (node (ref "U8") (pin "39") (pinfunction "GND_39") (pintype "input"))
      (node (ref "U9") (pin "13") (pinfunction "GND_13") (pintype "input"))
      (node (ref "USB1") (pin "0") (pinfunction "EH_0") (pintype "unspecified"))
      (node (ref "USB1") (pin "A1") (pinfunction "GND_A1") (pintype "unspecified"))
      (node (ref "USB1") (pin "A12") (pinfunction "GND_A12") (pintype "unspecified"))
      (node (ref "USB2") (pin "0") (pinfunction "EH_0") (pintype "unspecified"))
      (node (ref "USB2") (pin "A1") (pinfunction "GND_A1") (pintype "unspecified"))
      (node (ref "USB2") (pin "A12") (pinfunction "GND_A12") (pintype "unspecified"))
    )
    (net (code "83") (name "Net-(C17-Pad1)") (class "Default")
      (node (ref "C17") (pin "1") (pinfunction "1_1") (pintype "input"))
      (node (ref "R11") (pin "2") (pinfunction "2_2") (pintype "input"))
      (node (ref "R15") (pin "2") (pinfunction "2_2") (pintype "input"))
      (node (ref "SW2") (pin "1") (pinfunction "1_1") (pintype "unspecified"))
      (node (ref "SW2") (pin "2") (pinfunction "2_2") (pintype "unspecified"))
    )
    (net (code "84") (name "Net-(C18-Pad1)") (class "Default")
      (node (ref "C18") (pin "1") (pinfunction "1_1") (pintype "input"))
      (node (ref "R12") (pin "2") (pinfunction "2_2") (pintype "input"))
      (node (ref "R16") (pin "2") (pinfunction "2_2") (pintype "input"))
      (node (ref "SW3") (pin "1") (pinfunction "1_1") (pintype "unspecified"))
      (node (ref "SW3") (pin "2") (pinfunction "2_2") (pintype "unspecified"))
    )
    (net (code "85") (name "Net-(LED1-Pad2)") (class "Default")
      (node (ref "LED1") (pin "2") (pinfunction "2_2") (pintype "input"))
      (node (ref "LED2") (pin "2") (pinfunction "2_2") (pintype "input"))
      (node (ref "R7") (pin "1") (pinfunction "1_1") (pintype "input"))
    )
    (net (code "86") (name "Net-(LED3-Pad2)") (class "Default")
      (node (ref "LED3") (pin "2") (pinfunction "2_2") (pintype "input"))
      (node (ref "LED4") (pin "2") (pinfunction "2_2") (pintype "input"))
      (node (ref "R8") (pin "1") (pinfunction "1_1") (pintype "input"))
    )
    (net (code "87") (name "Net-(LED5-Pad2)") (class "Default")
      (node (ref "LED5") (pin "2") (pinfunction "2_2") (pintype "input"))
      (node (ref "R17") (pin "1") (pinfunction "1_1") (pintype "input"))
    )
    (net (code "88") (name "Net-(LED6-Pad2)") (class "Default")
      (node (ref "LED6") (pin "2") (pinfunction "2_2") (pintype "input"))
      (node (ref "R18") (pin "1") (pinfunction "1_1") (pintype "input"))
    )
    (net (code "89") (name "Net-(SW1-B1)") (class "Default")
      (node (ref "R1") (pin "1") (pinfunction "1_1") (pintype "input"))
      (node (ref "R4") (pin "2") (pinfunction "2_2") (pintype "input"))
      (node (ref "SW1") (pin "6") (pinfunction "B1_6") (pintype "input"))
    )
    (net (code "90") (name "Net-(SW1-B2)") (class "Default")
      (node (ref "R2") (pin "1") (pinfunction "1_1") (pintype "input"))
      (node (ref "R5") (pin "2") (pinfunction "2_2") (pintype "input"))
      (node (ref "SW1") (pin "5") (pinfunction "B2_5") (pintype "input"))
    )
    (net (code "91") (name "Net-(SW1-B3)") (class "Default")
      (node (ref "R3") (pin "1") (pinfunction "1_1") (pintype "input"))
      (node (ref "R6") (pin "2") (pinfunction "2_2") (pintype "input"))
      (node (ref "SW1") (pin "4") (pinfunction "B3_4") (pintype "input"))
    )
    (net (code "92") (name "Net-(U12-RESET)") (class "Default")
      (node (ref "U12") (pin "11") (pinfunction "SLEEP_11") (pintype "input"))
      (node (ref "U12") (pin "12") (pinfunction "RESET_12") (pintype "input"))
    )
    (net (code "93") (name "Net-(U13-RESET)") (class "Default")
      (node (ref "U13") (pin "11") (pinfunction "SLEEP_11") (pintype "input"))
      (node (ref "U13") (pin "12") (pinfunction "RESET_12") (pintype "input"))
    )
    (net (code "94") (name "Net-(U18-RESET)") (class "Default")
      (node (ref "U18") (pin "11") (pinfunction "SLEEP_11") (pintype "input"))
      (node (ref "U18") (pin "12") (pinfunction "RESET_12") (pintype "input"))
    )
    (net (code "95") (name "Net-(U19-RESET)") (class "Default")
      (node (ref "U19") (pin "11") (pinfunction "SLEEP_11") (pintype "input"))
      (node (ref "U19") (pin "12") (pinfunction "RESET_12") (pintype "input"))
    )
    (net (code "96") (name "Net-(U23-RESET)") (class "Default")
      (node (ref "U23") (pin "11") (pinfunction "SLEEP_11") (pintype "input"))
      (node (ref "U23") (pin "12") (pinfunction "RESET_12") (pintype "input"))
    )
    (net (code "97") (name "Net-(U24-RESET)") (class "Default")
      (node (ref "U24") (pin "11") (pinfunction "SLEEP_11") (pintype "input"))
      (node (ref "U24") (pin "12") (pinfunction "RESET_12") (pintype "input"))
    )
    (net (code "98") (name "Net-(U26-RESET)") (class "Default")
      (node (ref "U26") (pin "11") (pinfunction "SLEEP_11") (pintype "input"))
      (node (ref "U26") (pin "12") (pinfunction "RESET_12") (pintype "input"))
    )
    (net (code "99") (name "Net-(U27-RESET)") (class "Default")
      (node (ref "U27") (pin "11") (pinfunction "SLEEP_11") (pintype "input"))
      (node (ref "U27") (pin "12") (pinfunction "RESET_12") (pintype "input"))
    )
    (net (code "100") (name "VCC") (class "Default")
      (node (ref "C11") (pin "1") (pinfunction "1_1") (pintype "input"))
      (node (ref "C12") (pin "1") (pinfunction "1_1") (pintype "input"))
      (node (ref "C13") (pin "2") (pinfunction "2_2") (pintype "input"))
      (node (ref "C15") (pin "1") (pinfunction "1_1") (pintype "input"))
      (node (ref "C16") (pin "1") (pinfunction "1_1") (pintype "input"))
      (node (ref "C19") (pin "1") (pinfunction "1_1") (pintype "input"))
      (node (ref "C20") (pin "1") (pinfunction "1_1") (pintype "input"))
      (node (ref "C21") (pin "1") (pinfunction "1_1") (pintype "input"))
      (node (ref "C22") (pin "1") (pinfunction "1_1") (pintype "input"))
      (node (ref "C9") (pin "2") (pinfunction "2_2") (pintype "input"))
      (node (ref "D3") (pin "1") (pinfunction "K_1") (pintype "unspecified"))
      (node (ref "D4") (pin "1") (pinfunction "K_1") (pintype "unspecified"))
      (node (ref "U12") (pin "8") (pinfunction "VMOT_8") (pintype "input"))
      (node (ref "U13") (pin "8") (pinfunction "VMOT_8") (pintype "input"))
      (node (ref "U17") (pin "1") (pinfunction "IN_1") (pintype "input"))
      (node (ref "U18") (pin "8") (pinfunction "VMOT_8") (pintype "input"))
      (node (ref "U19") (pin "8") (pinfunction "VMOT_8") (pintype "input"))
      (node (ref "U23") (pin "8") (pinfunction "VMOT_8") (pintype "input"))
      (node (ref "U24") (pin "8") (pinfunction "VMOT_8") (pintype "input"))
      (node (ref "U26") (pin "8") (pinfunction "VMOT_8") (pintype "input"))
      (node (ref "U27") (pin "8") (pinfunction "VMOT_8") (pintype "input"))
      (node (ref "U28") (pin "1") (pinfunction "1_1") (pintype "unspecified"))
      (node (ref "U29") (pin "1") (pinfunction "1_1") (pintype "unspecified"))
      (node (ref "U7") (pin "1") (pinfunction "IN_1") (pintype "input"))
    )
    (net (code "101") (name "unconnected-(U2-RTS#-Pad4)") (class "Default")
      (node (ref "U2") (pin "4") (pinfunction "RTS#_4") (pintype "input+no_connect"))
    )
    (net (code "102") (name "unconnected-(U3-RTS#-Pad4)") (class "Default")
      (node (ref "U3") (pin "4") (pinfunction "RTS#_4") (pintype "input+no_connect"))
    )
    (net (code "103") (name "unconnected-(U8-BOOT1-PB2-Pad16)") (class "Default")
      (node (ref "U8") (pin "16") (pinfunction "BOOT1-PB2_16") (pintype "input+no_connect"))
    )
    (net (code "104") (name "unconnected-(U8-KEY0-PA0-Pad6)") (class "Default")
      (node (ref "U8") (pin "6") (pinfunction "KEY0-PA0_6") (pintype "input+no_connect"))
    )
    (net (code "105") (name "unconnected-(U8-NRST-Pad5)") (class "Default")
      (node (ref "U8") (pin "5") (pinfunction "NRST_5") (pintype "input+no_connect"))
    )
    (net (code "106") (name "unconnected-(U8-PA11-Pad28)") (class "Default")
      (node (ref "U8") (pin "28") (pinfunction "PA11_28") (pintype "input+no_connect"))
    )
    (net (code "107") (name "unconnected-(U8-PA12-Pad29)") (class "Default")
      (node (ref "U8") (pin "29") (pinfunction "PA12_29") (pintype "input+no_connect"))
    )
    (net (code "108") (name "unconnected-(U8-PC13-Pad2)") (class "Default")
      (node (ref "U8") (pin "2") (pinfunction "PC13_2") (pintype "input+no_connect"))
    )
    (net (code "109") (name "unconnected-(U8-VBAT-Pad1)") (class "Default")
      (node (ref "U8") (pin "1") (pinfunction "VBAT_1") (pintype "input+no_connect"))
    )
    (net (code "110") (name "unconnected-(U9-T_CLK-Pad5)") (class "Default")
      (node (ref "U9") (pin "5") (pinfunction "T_CLK_5") (pintype "input+no_connect"))
    )
    (net (code "111") (name "unconnected-(U9-T_CS-Pad4)") (class "Default")
      (node (ref "U9") (pin "4") (pinfunction "T_CS_4") (pintype "input+no_connect"))
    )
    (net (code "112") (name "unconnected-(U9-T_DIN-Pad3)") (class "Default")
      (node (ref "U9") (pin "3") (pinfunction "T_DIN_3") (pintype "input+no_connect"))
    )
    (net (code "113") (name "unconnected-(U9-T_DIO-Pad2)") (class "Default")
      (node (ref "U9") (pin "2") (pinfunction "T_DIO_2") (pintype "input+no_connect"))
    )
    (net (code "114") (name "unconnected-(U9-T_IRQ-Pad1)") (class "Default")
      (node (ref "U9") (pin "1") (pinfunction "T_IRQ_1") (pintype "input+no_connect"))
    )
    (net (code "115") (name "unconnected-(U14-Pad9)") (class "Default")
      (node (ref "U14") (pin "9") (pinfunction "9_9") (pintype "input+no_connect"))
    )
    (net (code "116") (name "unconnected-(USB1-CC1-PadA5)") (class "Default")
      (node (ref "USB1") (pin "A5") (pinfunction "CC1_A5") (pintype "unspecified+no_connect"))
    )
    (net (code "117") (name "unconnected-(USB1-CC2-PadB5)") (class "Default")
      (node (ref "USB1") (pin "B5") (pinfunction "CC2_B5") (pintype "unspecified+no_connect"))
    )
    (net (code "118") (name "unconnected-(USB1-SBU1-PadA8)") (class "Default")
      (node (ref "USB1") (pin "A8") (pinfunction "SBU1_A8") (pintype "unspecified+no_connect"))
    )
    (net (code "119") (name "unconnected-(USB1-SBU2-PadB8)") (class "Default")
      (node (ref "USB1") (pin "B8") (pinfunction "SBU2_B8") (pintype "unspecified+no_connect"))
    )
    (net (code "120") (name "unconnected-(USB2-CC1-PadA5)") (class "Default")
      (node (ref "USB2") (pin "A5") (pinfunction "CC1_A5") (pintype "unspecified+no_connect"))
    )
    (net (code "121") (name "unconnected-(USB2-CC2-PadB5)") (class "Default")
      (node (ref "USB2") (pin "B5") (pinfunction "CC2_B5") (pintype "unspecified+no_connect"))
    )
    (net (code "122") (name "unconnected-(USB2-SBU1-PadA8)") (class "Default")
      (node (ref "USB2") (pin "A8") (pinfunction "SBU1_A8") (pintype "unspecified+no_connect"))
    )
    (net (code "123") (name "unconnected-(USB2-SBU2-PadB8)") (class "Default")
      (node (ref "USB2") (pin "B8") (pinfunction "SBU2_B8") (pintype "unspecified+no_connect"))
    )
  )
)
